# ultrasonic_imu_sensor.net
KiCad netlist of a schematic drawn in Altium Designer
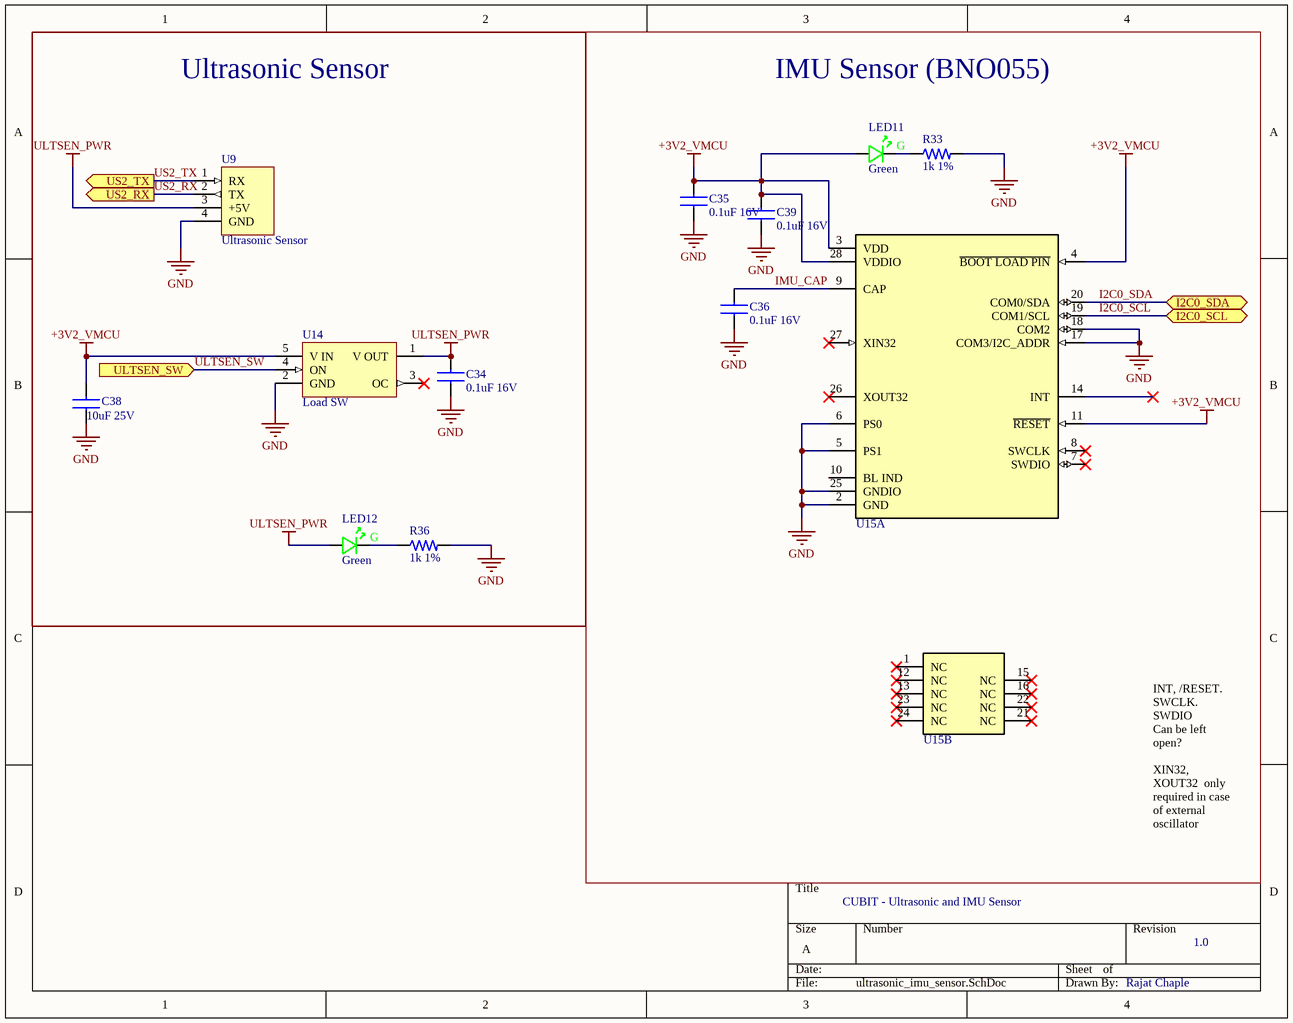
[diagram p0: ultrasonic_imu_sensor.SchDoc]

(export (version "E")
  (design (tool "Eeschema 10.0.6"))
  (components
    (comp (ref "C34")
      (value "0.1uF 16V")
      (footprint "CAP_0603_1MM")
      (description "Cap Ceramic 0.1uF 16V X7R 10% SMD 0603 125°C Paper T/R")
      (fields
        (field (name "MANUFACTURER") "KEMET")
        (field (name "MANUFACTURER PART NUMBER") "C0805C104K4RACAUTO")
      )
      (libsource (lib "LPEDT_proj_lib") (part "C0805C104K4RACAUTO"))
    )
    (comp (ref "C35")
      (value "0.1uF 16V")
      (footprint "LPEDT_proj_lib:CAP_0603_1MM")
      (description "Cap Ceramic 0.1uF 16V X7R 10% SMD 0603 125°C Paper T/R")
      (fields
        (field (name "MANUFACTURER") "KEMET")
        (field (name "MANUFACTURER PART NUMBER") "C0805C104K4RACAUTO")
      )
      (libsource (lib "LPEDT_proj_lib") (part "C0805C104K4RACAUTO"))
    )
    (comp (ref "C36")
      (value "0.1uF 16V")
      (footprint "LPEDT_proj_lib:CAP_0603_1MM")
      (description "Cap Ceramic 0.1uF 16V X7R 10% SMD 0603 125°C Paper T/R")
      (fields
        (field (name "MANUFACTURER") "KEMET")
        (field (name "MANUFACTURER PART NUMBER") "C0805C104K4RACAUTO")
      )
      (libsource (lib "LPEDT_proj_lib") (part "C0805C104K4RACAUTO"))
    )
    (comp (ref "C38")
      (value "10uF 25V")
      (footprint "LPEDT_proj_lib:CAP_0805_02X125")
      (description "Cap 0805 25 V 10 uF ±20% Tolerance X5R Monolithic Ceramic Chip Capacitor")
      (fields
        (field (name "MANUFACTURER") "Murata")
        (field (name "MANUFACTURER PART NUMBER") "GRM21BR61E106KA73K")
      )
      (libsource (lib "LPEDT_proj_lib") (part "GRM21BR61E106KA73K"))
    )
    (comp (ref "C39")
      (value "0.1uF 16V")
      (footprint "LPEDT_proj_lib:CAP_0603_1MM")
      (description "Cap Ceramic 0.1uF 16V X7R 10% SMD 0603 125°C Paper T/R")
      (fields
        (field (name "MANUFACTURER") "KEMET")
        (field (name "MANUFACTURER PART NUMBER") "C0805C104K4RACAUTO")
      )
      (libsource (lib "LPEDT_proj_lib") (part "C0805C104K4RACAUTO"))
    )
    (comp (ref "LED11")
      (value "Green")
      (footprint "LED_0603_RED_WL-SMCW")
      (description "Led Green Clear 0603 SMD")
      (fields
        (field (name "MANUFACTURER") "QT-Brightek")
        (field (name "MANUFACTURER PART NUMBER") "QBLP601-AG1")
      )
      (libsource (lib "LPEDT_proj_lib") (part "QBLP601-AG1"))
    )
    (comp (ref "LED12")
      (value "Green")
      (footprint "LED_0603_RED_WL-SMCW")
      (description "Led Green Clear 0603 SMD")
      (fields
        (field (name "MANUFACTURER") "QT-Brightek")
        (field (name "MANUFACTURER PART NUMBER") "QBLP601-AG1")
      )
      (libsource (lib "LPEDT_proj_lib") (part "QBLP601-AG1"))
    )
    (comp (ref "R33")
      (value "1k 1%")
      (footprint "2_Chip_0603_RMCF")
      (description "Res 1K Ohm 1% 0.1W(1/10W) ±100ppm/C Pad SMD Automotive T/R")
      (fields
        (field (name "MANUFACTURER") "Stackpole Electronics")
        (field (name "MANUFACTURER PART NUMBER") "RMCF0603FT1K00")
      )
      (libsource (lib "LPEDT_proj_lib") (part "RMCF0603FT1K00"))
    )
    (comp (ref "R36")
      (value "1k 1%")
      (footprint "2_Chip_0603_RMCF")
      (description "Res 1K Ohm 1% 0.1W(1/10W) ±100ppm/C Pad SMD Automotive T/R")
      (fields
        (field (name "MANUFACTURER") "Stackpole Electronics")
        (field (name "MANUFACTURER PART NUMBER") "RMCF0603FT1K00")
      )
      (libsource (lib "LPEDT_proj_lib") (part "RMCF0603FT1K00"))
    )
    (comp (ref "U9")
      (value "Ultrasonic Sensor")
      (footprint "4_PIN_100MIL")
      (libsource (lib "LPEDT_proj_lib") (part "Ultrasonic Sensor"))
    )
    (comp (ref "U14")
      (value "Load SW")
      (footprint "SOT65P210X110-5N")
      (description "5.5-V, 0.1-A, 500-mΩ, load switch with current limit and active low enable 5-SC70 -40 to 85")
      (fields
        (field (name "MANUFACTURER") "Texas Instruments")
        (field (name "MANUFACTURER PART NUMBER") "TPS22942DCKR")
      )
      (libsource (lib "LPEDT_proj_lib") (part "TPS22942DCKR"))
    )
    (comp (ref "U15")
      (value "BNO005")
      (footprint "LGA28R50P4X10_380X520X100")
      (libsource (lib "LPEDT_proj_lib") (part "BNO055"))
    )
  )
  (nets
    (net (code "1") (name "+3V2_VMCU") (class "Default")
      (node (ref "C35") (pin "1") (pinfunction "1_1") (pintype "passive"))
      (node (ref "C38") (pin "1") (pinfunction "1_1") (pintype "passive"))
      (node (ref "C39") (pin "1") (pinfunction "1_1") (pintype "passive"))
      (node (ref "LED11") (pin "A") (pinfunction "A_A") (pintype "passive"))
      (node (ref "U14") (pin "5") (pinfunction "V_IN_5") (pintype "power_in"))
      (node (ref "U15") (pin "11") (pinfunction "~{RESET}_11") (pintype "input"))
      (node (ref "U15") (pin "28") (pinfunction "VDDIO_28") (pintype "power_in"))
      (node (ref "U15") (pin "3") (pinfunction "VDD_3") (pintype "power_in"))
      (node (ref "U15") (pin "4") (pinfunction "~{BOOT_LOAD_PIN}_4") (pintype "input"))
    )
    (net (code "2") (name "/I2C0_SCL") (class "Default")
      (node (ref "U15") (pin "19") (pinfunction "COM1/SCL_19") (pintype "bidirectional"))
    )
    (net (code "3") (name "/I2C0_SDA") (class "Default")
      (node (ref "U15") (pin "20") (pinfunction "COM0/SDA_20") (pintype "bidirectional"))
    )
    (net (code "4") (name "/IMU_CAP") (class "Default")
      (node (ref "C36") (pin "1") (pinfunction "1_1") (pintype "passive"))
      (node (ref "U15") (pin "9") (pinfunction "CAP_9") (pintype "passive"))
    )
    (net (code "5") (name "/ULTSEN_SW") (class "Default")
      (node (ref "U14") (pin "4") (pinfunction "ON_4") (pintype "input"))
    )
    (net (code "6") (name "/US2_RX") (class "Default")
      (node (ref "U9") (pin "2") (pinfunction "TX_2") (pintype "output"))
    )
    (net (code "7") (name "/US2_TX") (class "Default")
      (node (ref "U9") (pin "1") (pinfunction "RX_1") (pintype "input"))
    )
    (net (code "8") (name "GND") (class "Default")
      (node (ref "C34") (pin "2") (pinfunction "2_2") (pintype "passive"))
      (node (ref "C35") (pin "2") (pinfunction "2_2") (pintype "passive"))
      (node (ref "C36") (pin "2") (pinfunction "2_2") (pintype "passive"))
      (node (ref "C38") (pin "2") (pinfunction "2_2") (pintype "passive"))
      (node (ref "C39") (pin "2") (pinfunction "2_2") (pintype "passive"))
      (node (ref "R33") (pin "2") (pinfunction "2_2") (pintype "passive"))
      (node (ref "R36") (pin "2") (pinfunction "2_2") (pintype "passive"))
      (node (ref "U14") (pin "2") (pinfunction "GND_2") (pintype "power_in"))
      (node (ref "U15") (pin "17") (pinfunction "COM3/I2C_ADDR_17") (pintype "input"))
      (node (ref "U15") (pin "18") (pinfunction "COM2_18") (pintype "bidirectional"))
      (node (ref "U15") (pin "2") (pinfunction "GND_2") (pintype "power_in"))
      (node (ref "U15") (pin "25") (pinfunction "GNDIO_25") (pintype "power_in"))
      (node (ref "U15") (pin "5") (pinfunction "PS1_5") (pintype "power_in"))
      (node (ref "U15") (pin "6") (pinfunction "PS0_6") (pintype "power_in"))
      (node (ref "U9") (pin "4") (pinfunction "GND_4") (pintype "power_in"))
    )
    (net (code "9") (name "Net-(LED11-PadC)") (class "Default")
      (node (ref "LED11") (pin "C") (pinfunction "C_C") (pintype "passive"))
      (node (ref "R33") (pin "1") (pinfunction "1_1") (pintype "passive"))
    )
    (net (code "10") (name "Net-(LED12-PadC)") (class "Default")
      (node (ref "LED12") (pin "C") (pinfunction "C_C") (pintype "passive"))
      (node (ref "R36") (pin "1") (pinfunction "1_1") (pintype "passive"))
    )
    (net (code "11") (name "ULTSEN_PWR") (class "Default")
      (node (ref "C34") (pin "1") (pinfunction "1_1") (pintype "passive"))
      (node (ref "LED12") (pin "A") (pinfunction "A_A") (pintype "passive"))
      (node (ref "U14") (pin "1") (pinfunction "V_OUT_1") (pintype "power_in"))
      (node (ref "U9") (pin "3") (pinfunction "+5V_3") (pintype "power_in"))
    )
    (net (code "12") (name "unconnected-(U14-OC-Pad3)") (class "Default")
      (node (ref "U14") (pin "3") (pinfunction "OC_3") (pintype "output+no_connect"))
    )
    (net (code "13") (name "unconnected-(U15A-BL_IND-Pad10)") (class "Default")
      (node (ref "U15") (pin "10") (pinfunction "BL_IND_10") (pintype "power_in"))
    )
    (net (code "14") (name "unconnected-(U15A-INT-Pad14)") (class "Default")
      (node (ref "U15") (pin "14") (pinfunction "INT_14") (pintype "passive+no_connect"))
    )
    (net (code "15") (name "unconnected-(U15A-SWCLK-Pad8)") (class "Default")
      (node (ref "U15") (pin "8") (pinfunction "SWCLK_8") (pintype "input+no_connect"))
    )
    (net (code "16") (name "unconnected-(U15A-SWDIO-Pad7)") (class "Default")
      (node (ref "U15") (pin "7") (pinfunction "SWDIO_7") (pintype "bidirectional+no_connect"))
    )
    (net (code "17") (name "unconnected-(U15A-XIN32-Pad27)") (class "Default")
      (node (ref "U15") (pin "27") (pinfunction "XIN32_27") (pintype "input+no_connect"))
    )
    (net (code "18") (name "unconnected-(U15A-XOUT32-Pad26)") (class "Default")
      (node (ref "U15") (pin "26") (pinfunction "XOUT32_26") (pintype "passive+no_connect"))
    )
    (net (code "19") (name "unconnected-(U15B-NC-Pad1)") (class "Default")
      (node (ref "U15") (pin "1") (pinfunction "NC_1") (pintype "passive+no_connect"))
    )
    (net (code "20") (name "unconnected-(U15B-NC-Pad12)") (class "Default")
      (node (ref "U15") (pin "12") (pinfunction "NC_12") (pintype "passive+no_connect"))
    )
    (net (code "21") (name "unconnected-(U15B-NC-Pad13)") (class "Default")
      (node (ref "U15") (pin "13") (pinfunction "NC_13") (pintype "passive+no_connect"))
    )
    (net (code "22") (name "unconnected-(U15B-NC-Pad15)") (class "Default")
      (node (ref "U15") (pin "15") (pinfunction "NC_15") (pintype "passive+no_connect"))
    )
    (net (code "23") (name "unconnected-(U15B-NC-Pad16)") (class "Default")
      (node (ref "U15") (pin "16") (pinfunction "NC_16") (pintype "passive+no_connect"))
    )
    (net (code "24") (name "unconnected-(U15B-NC-Pad21)") (class "Default")
      (node (ref "U15") (pin "21") (pinfunction "NC_21") (pintype "passive+no_connect"))
    )
    (net (code "25") (name "unconnected-(U15B-NC-Pad22)") (class "Default")
      (node (ref "U15") (pin "22") (pinfunction "NC_22") (pintype "passive+no_connect"))
    )
    (net (code "26") (name "unconnected-(U15B-NC-Pad23)") (class "Default")
      (node (ref "U15") (pin "23") (pinfunction "NC_23") (pintype "passive+no_connect"))
    )
    (net (code "27") (name "unconnected-(U15B-NC-Pad24)") (class "Default")
      (node (ref "U15") (pin "24") (pinfunction "NC_24") (pintype "passive+no_connect"))
    )
  )
)
